# uC-Board.net
KiCad netlist of a schematic drawn in EAGLE
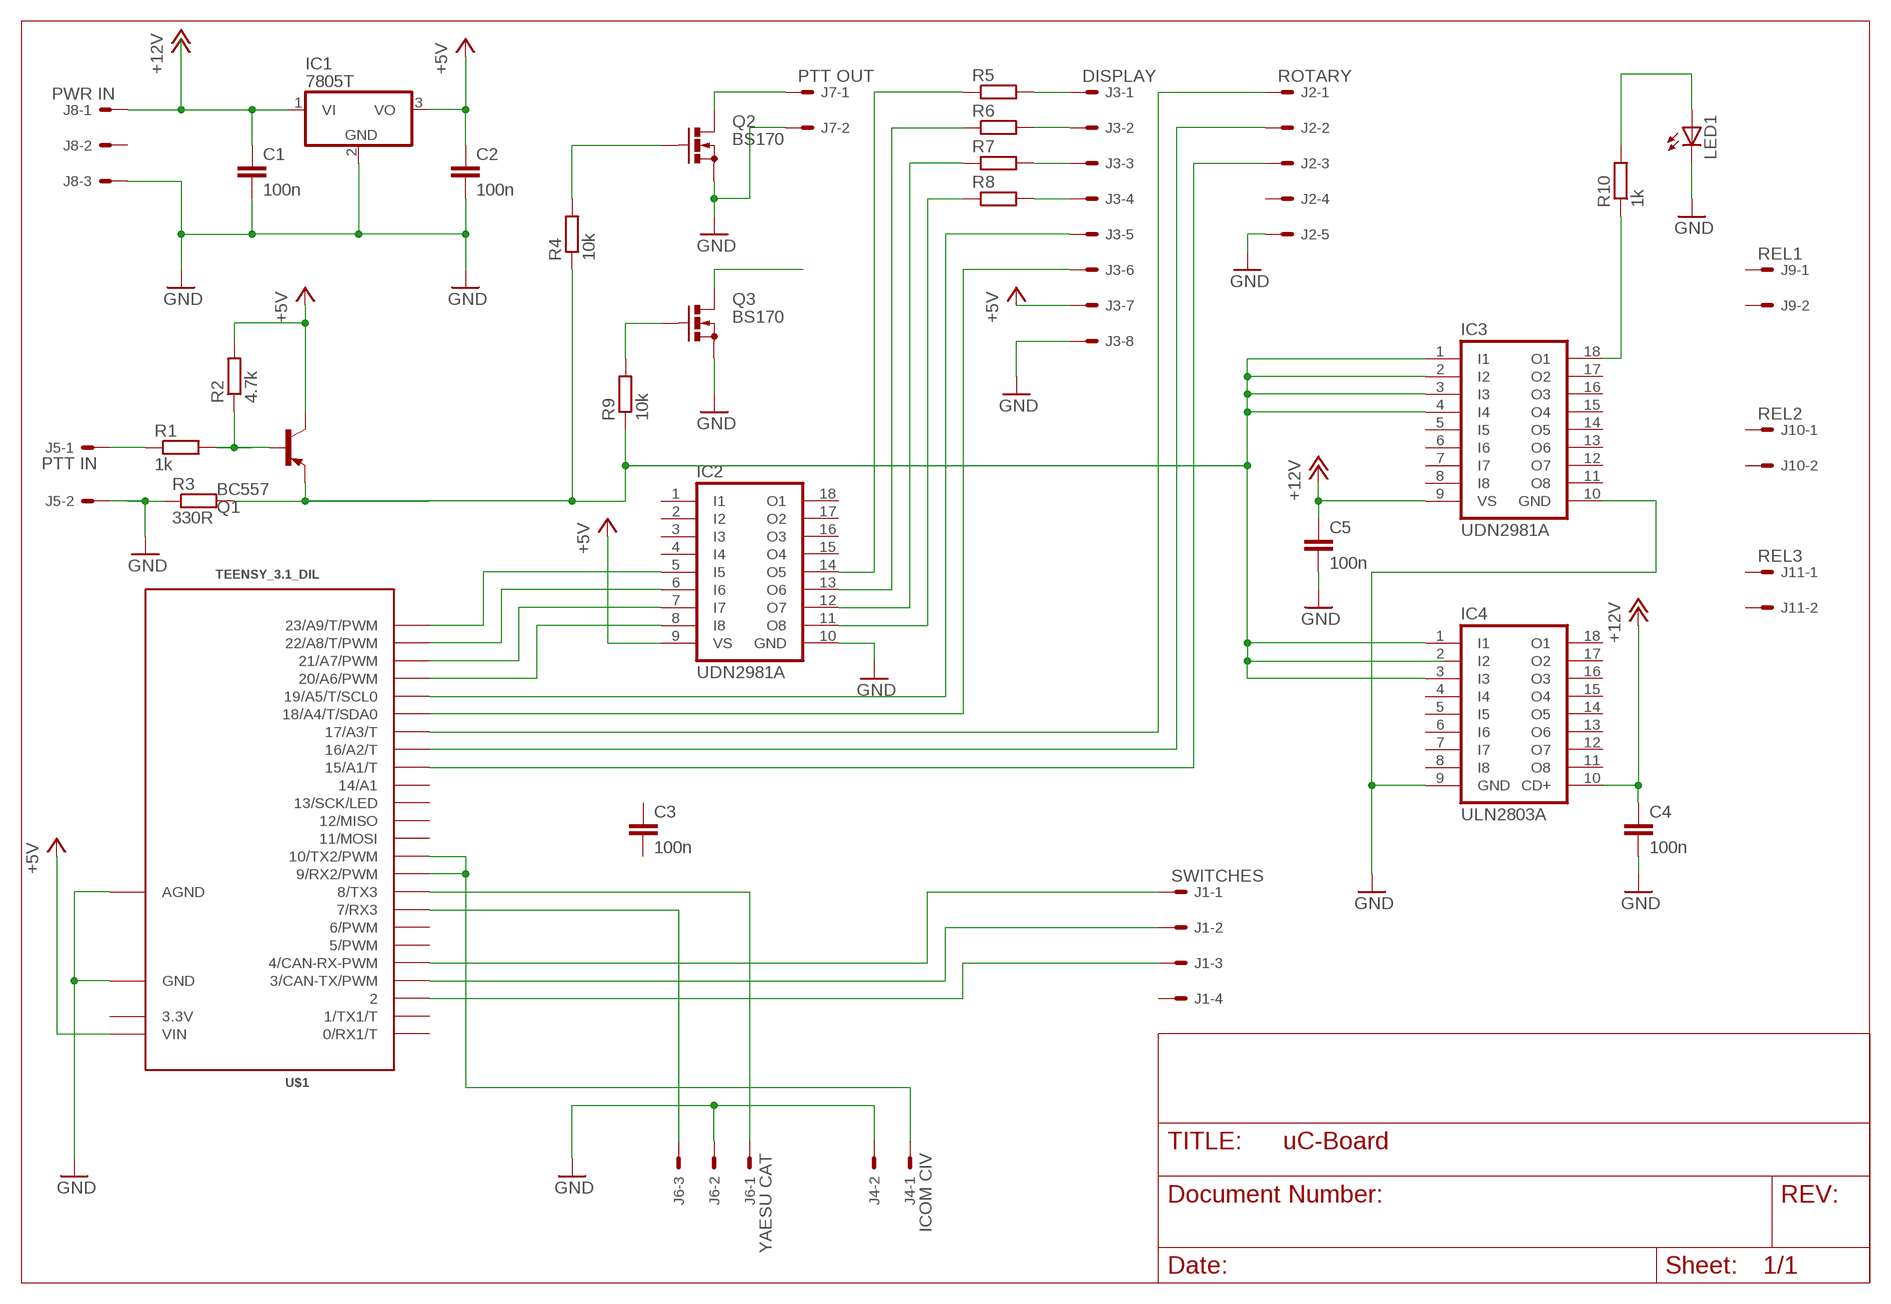
[diagram p0: schematic, sheet 1]

(export (version "E")
  (design (tool "Eeschema 10.0.6"))
  (components
    (comp (ref "C1")
      (value "100n")
      (footprint "eagle-import:C025-025X050")
      (libsource (lib "eagle-import") (part "C-EU025-025X050"))
    )
    (comp (ref "C2")
      (value "100n")
      (footprint "eagle-import:C025-025X050")
      (libsource (lib "eagle-import") (part "C-EU025-025X050"))
    )
    (comp (ref "C3")
      (value "100n")
      (footprint "eagle-import:C025-025X050")
      (libsource (lib "eagle-import") (part "C-EU025-025X050"))
    )
    (comp (ref "C4")
      (value "100n")
      (footprint "eagle-import:C025-025X050")
      (libsource (lib "eagle-import") (part "C-EU025-025X050"))
    )
    (comp (ref "C5")
      (value "100n")
      (footprint "eagle-import:C025-025X050")
      (libsource (lib "eagle-import") (part "C-EU025-025X050"))
    )
    (comp (ref "IC1")
      (value "7805T")
      (footprint "eagle-import:TO220H")
      (libsource (lib "eagle-import") (part "78T05"))
    )
    (comp (ref "IC2")
      (value "UDN2981A")
      (footprint "eagle-import:DIL18")
      (libsource (lib "eagle-import") (part "UDN298A1"))
    )
    (comp (ref "IC3")
      (value "UDN2981A")
      (footprint "eagle-import:DIL18")
      (libsource (lib "eagle-import") (part "UDN298A1"))
    )
    (comp (ref "IC4")
      (value "ULN2803A")
      (footprint "eagle-import:DIL18")
      (libsource (lib "eagle-import") (part "ULN2803A"))
    )
    (comp (ref "J1")
      (value "SWITCHES")
      (footprint "eagle-import:6410-04")
      (libsource (lib "eagle-import") (part "22-?-0427-2041"))
    )
    (comp (ref "J2")
      (value "ROTARY")
      (footprint "eagle-import:6410-05")
      (libsource (lib "eagle-import") (part "22-?-0527-2051"))
    )
    (comp (ref "J3")
      (value "DISPLAY")
      (footprint "eagle-import:6410-08")
      (libsource (lib "eagle-import") (part "22-?-0827-2081"))
    )
    (comp (ref "J4")
      (value "ICOM CIV")
      (footprint "eagle-import:6410-02")
      (libsource (lib "eagle-import") (part "22-?-0227-2021"))
    )
    (comp (ref "J5")
      (value "PTT IN")
      (footprint "eagle-import:6410-02")
      (libsource (lib "eagle-import") (part "22-?-0227-2021"))
    )
    (comp (ref "J6")
      (value "YAESU CAT")
      (footprint "eagle-import:6410-03")
      (libsource (lib "eagle-import") (part "22-?-0327-2031"))
    )
    (comp (ref "J7")
      (value "PTT OUT")
      (footprint "eagle-import:6410-02")
      (libsource (lib "eagle-import") (part "22-?-0227-2021"))
    )
    (comp (ref "J8")
      (value "PWR IN")
      (footprint "eagle-import:22-23-2031")
      (fields (field (name "MF") "MOLEX") (field (name "MPN") "22-23-2031"))
      (libsource (lib "eagle-import") (part "22-23-2031"))
    )
    (comp (ref "J9")
      (value "REL1")
      (footprint "eagle-import:6410-02")
      (libsource (lib "eagle-import") (part "22-?-0227-2021"))
    )
    (comp (ref "J10")
      (value "REL2")
      (footprint "eagle-import:6410-02")
      (libsource (lib "eagle-import") (part "22-?-0227-2021"))
    )
    (comp (ref "J11")
      (value "REL3")
      (footprint "eagle-import:6410-02")
      (libsource (lib "eagle-import") (part "22-?-0227-2021"))
    )
    (comp (ref "LED1")
      (value "LED5MM")
      (footprint "eagle-import:LED5MM")
      (libsource (lib "eagle-import") (part "LED5MM"))
    )
    (comp (ref "Q1")
      (value "BC557")
      (footprint "eagle-import:TO92")
      (libsource (lib "eagle-import") (part "BC557"))
    )
    (comp (ref "Q2")
      (value "BS170")
      (footprint "eagle-import:SOT54E")
      (libsource (lib "eagle-import") (part "BS170"))
    )
    (comp (ref "Q3")
      (value "BS170")
      (footprint "eagle-import:SOT54E")
      (libsource (lib "eagle-import") (part "BS170"))
    )
    (comp (ref "R1")
      (value "1k")
      (footprint "eagle-import:0207_10")
      (libsource (lib "eagle-import") (part "R-EU_0207/10"))
    )
    (comp (ref "R2")
      (value "4.7k")
      (footprint "eagle-import:0207_10")
      (libsource (lib "eagle-import") (part "R-EU_0207/10"))
    )
    (comp (ref "R3")
      (value "330R")
      (footprint "eagle-import:0207_10")
      (libsource (lib "eagle-import") (part "R-EU_0207/10"))
    )
    (comp (ref "R4")
      (value "10k")
      (footprint "eagle-import:0207_10")
      (libsource (lib "eagle-import") (part "R-EU_0207/10"))
    )
    (comp (ref "R5")
      (value "R-EU_0207/10")
      (footprint "eagle-import:0207_10")
      (libsource (lib "eagle-import") (part "R-EU_0207/10"))
    )
    (comp (ref "R6")
      (value "R-EU_0207/10")
      (footprint "eagle-import:0207_10")
      (libsource (lib "eagle-import") (part "R-EU_0207/10"))
    )
    (comp (ref "R7")
      (value "R-EU_0207/10")
      (footprint "eagle-import:0207_10")
      (libsource (lib "eagle-import") (part "R-EU_0207/10"))
    )
    (comp (ref "R8")
      (value "R-EU_0207/10")
      (footprint "eagle-import:0207_10")
      (libsource (lib "eagle-import") (part "R-EU_0207/10"))
    )
    (comp (ref "R9")
      (value "10k")
      (footprint "eagle-import:0207_10")
      (libsource (lib "eagle-import") (part "R-EU_0207/10"))
    )
    (comp (ref "R10")
      (value "1k")
      (footprint "eagle-import:0207_10")
      (libsource (lib "eagle-import") (part "R-EU_0207/10"))
    )
    (comp (ref "U$1")
      (value "TEENSY_3.1_DIL")
      (footprint "eagle-import:TEENSY3-DIL")
      (libsource (lib "eagle-import") (part "TEENSY_3.1_DIL"))
    )
  )
  (nets
    (net (code "1") (name "+5V") (class "Default")
      (node (ref "C2") (pin "1") (pinfunction "1_1") (pintype "passive"))
      (node (ref "IC1") (pin "3") (pinfunction "VO_3") (pintype "passive"))
      (node (ref "IC2") (pin "9") (pinfunction "VS_9") (pintype "passive"))
      (node (ref "J3") (pin "7") (pinfunction "S_7") (pintype "passive"))
      (node (ref "Q1") (pin "3") (pinfunction "C_3") (pintype "passive"))
      (node (ref "R2") (pin "2") (pinfunction "2_2") (pintype "passive"))
      (node (ref "U$1") (pin "VIN") (pinfunction "VIN_VIN") (pintype "power_in"))
    )
    (net (code "2") (name "+12V") (class "Default")
      (node (ref "C1") (pin "1") (pinfunction "1_1") (pintype "passive"))
      (node (ref "C4") (pin "1") (pinfunction "1_1") (pintype "passive"))
      (node (ref "C5") (pin "1") (pinfunction "1_1") (pintype "passive"))
      (node (ref "IC1") (pin "1") (pinfunction "VI_1") (pintype "input"))
      (node (ref "IC3") (pin "9") (pinfunction "VS_9") (pintype "passive"))
      (node (ref "IC4") (pin "10") (pinfunction "CD+_10") (pintype "passive"))
      (node (ref "J8") (pin "1") (pinfunction "S_1") (pintype "passive"))
    )
    (net (code "3") (name "/3.3V") (class "Default")
      (node (ref "U$1") (pin "3.3V") (pinfunction "3.3V_3.3V") (pintype "power_in"))
    )
    (net (code "4") (name "GND") (class "Default")
      (node (ref "C1") (pin "2") (pinfunction "2_2") (pintype "passive"))
      (node (ref "C2") (pin "2") (pinfunction "2_2") (pintype "passive"))
      (node (ref "C4") (pin "2") (pinfunction "2_2") (pintype "passive"))
      (node (ref "C5") (pin "2") (pinfunction "2_2") (pintype "passive"))
      (node (ref "IC1") (pin "2") (pinfunction "GND_2") (pintype "passive"))
      (node (ref "IC2") (pin "10") (pinfunction "GND_10") (pintype "power_in"))
      (node (ref "IC3") (pin "10") (pinfunction "GND_10") (pintype "power_in"))
      (node (ref "IC4") (pin "9") (pinfunction "GND_9") (pintype "power_in"))
      (node (ref "J2") (pin "5") (pinfunction "S_5") (pintype "passive"))
      (node (ref "J3") (pin "8") (pinfunction "S_8") (pintype "passive"))
      (node (ref "J4") (pin "2") (pinfunction "S_2") (pintype "passive"))
      (node (ref "J5") (pin "2") (pinfunction "S_2") (pintype "passive"))
      (node (ref "J6") (pin "2") (pinfunction "S_2") (pintype "passive"))
      (node (ref "J7") (pin "2") (pinfunction "S_2") (pintype "passive"))
      (node (ref "J8") (pin "3") (pinfunction "S_3") (pintype "passive"))
      (node (ref "LED1") (pin "K") (pinfunction "C_K") (pintype "passive"))
      (node (ref "Q2") (pin "S") (pinfunction "S_S") (pintype "passive"))
      (node (ref "Q3") (pin "S") (pinfunction "S_S") (pintype "passive"))
      (node (ref "R3") (pin "1") (pinfunction "1_1") (pintype "passive"))
      (node (ref "U$1") (pin "AGND") (pinfunction "AGND_AGND") (pintype "power_in"))
      (node (ref "U$1") (pin "GND") (pinfunction "GND_GND") (pintype "power_in"))
    )
    (net (code "5") (name "Net-(IC2-I5)") (class "Default")
      (node (ref "IC2") (pin "5") (pinfunction "I5_5") (pintype "input"))
      (node (ref "U$1") (pin "23/A9") (pinfunction "23/A9/T/PWM_23/A9") (pintype "bidirectional"))
    )
    (net (code "6") (name "Net-(IC2-I6)") (class "Default")
      (node (ref "IC2") (pin "6") (pinfunction "I6_6") (pintype "input"))
      (node (ref "U$1") (pin "22/A8") (pinfunction "22/A8/T/PWM_22/A8") (pintype "bidirectional"))
    )
    (net (code "7") (name "Net-(IC2-I7)") (class "Default")
      (node (ref "IC2") (pin "7") (pinfunction "I7_7") (pintype "input"))
      (node (ref "U$1") (pin "21/A7") (pinfunction "21/A7/PWM_21/A7") (pintype "bidirectional"))
    )
    (net (code "8") (name "Net-(IC2-I8)") (class "Default")
      (node (ref "IC2") (pin "8") (pinfunction "I8_8") (pintype "input"))
      (node (ref "U$1") (pin "20/A6") (pinfunction "20/A6/PWM_20/A6") (pintype "bidirectional"))
    )
    (net (code "9") (name "Net-(IC2-O5)") (class "Default")
      (node (ref "IC2") (pin "14") (pinfunction "O5_14") (pintype "open_collector"))
      (node (ref "R5") (pin "1") (pinfunction "1_1") (pintype "passive"))
    )
    (net (code "10") (name "Net-(IC2-O6)") (class "Default")
      (node (ref "IC2") (pin "13") (pinfunction "O6_13") (pintype "open_collector"))
      (node (ref "R6") (pin "1") (pinfunction "1_1") (pintype "passive"))
    )
    (net (code "11") (name "Net-(IC2-O7)") (class "Default")
      (node (ref "IC2") (pin "12") (pinfunction "O7_12") (pintype "open_collector"))
      (node (ref "R7") (pin "1") (pinfunction "1_1") (pintype "passive"))
    )
    (net (code "12") (name "Net-(IC2-O8)") (class "Default")
      (node (ref "IC2") (pin "11") (pinfunction "O8_11") (pintype "open_collector"))
      (node (ref "R8") (pin "1") (pinfunction "1_1") (pintype "passive"))
    )
    (net (code "13") (name "Net-(IC3-I1)") (class "Default")
      (node (ref "IC3") (pin "1") (pinfunction "I1_1") (pintype "input"))
      (node (ref "IC3") (pin "2") (pinfunction "I2_2") (pintype "input"))
      (node (ref "IC3") (pin "3") (pinfunction "I3_3") (pintype "input"))
      (node (ref "IC3") (pin "4") (pinfunction "I4_4") (pintype "input"))
      (node (ref "IC4") (pin "1") (pinfunction "I1_1") (pintype "input"))
      (node (ref "IC4") (pin "3") (pinfunction "I3_3") (pintype "input"))
      (node (ref "Q1") (pin "1") (pinfunction "E_1") (pintype "passive"))
      (node (ref "R3") (pin "2") (pinfunction "2_2") (pintype "passive"))
      (node (ref "R4") (pin "1") (pinfunction "1_1") (pintype "passive"))
      (node (ref "R9") (pin "1") (pinfunction "1_1") (pintype "passive"))
    )
    (net (code "14") (name "Net-(IC3-O1)") (class "Default")
      (node (ref "IC3") (pin "18") (pinfunction "O1_18") (pintype "open_collector"))
      (node (ref "R10") (pin "1") (pinfunction "1_1") (pintype "passive"))
    )
    (net (code "15") (name "Net-(J1A-S)") (class "Default")
      (node (ref "J1") (pin "1") (pinfunction "S_1") (pintype "passive"))
      (node (ref "U$1") (pin "4") (pinfunction "4/CAN-RX-PWM_4") (pintype "bidirectional"))
    )
    (net (code "16") (name "Net-(J1B-S)") (class "Default")
      (node (ref "J1") (pin "2") (pinfunction "S_2") (pintype "passive"))
      (node (ref "U$1") (pin "3") (pinfunction "3/CAN-TX/PWM_3") (pintype "bidirectional"))
    )
    (net (code "17") (name "Net-(J1C-S)") (class "Default")
      (node (ref "J1") (pin "3") (pinfunction "S_3") (pintype "passive"))
      (node (ref "U$1") (pin "2") (pinfunction "2_2") (pintype "bidirectional"))
    )
    (net (code "18") (name "Net-(J2A-S)") (class "Default")
      (node (ref "J2") (pin "1") (pinfunction "S_1") (pintype "passive"))
      (node (ref "U$1") (pin "17/A3") (pinfunction "17/A3/T_17/A3") (pintype "bidirectional"))
    )
    (net (code "19") (name "Net-(J2B-S)") (class "Default")
      (node (ref "J2") (pin "2") (pinfunction "S_2") (pintype "passive"))
      (node (ref "U$1") (pin "16/A2") (pinfunction "16/A2/T_16/A2") (pintype "bidirectional"))
    )
    (net (code "20") (name "Net-(J2C-S)") (class "Default")
      (node (ref "J2") (pin "3") (pinfunction "S_3") (pintype "passive"))
      (node (ref "U$1") (pin "15/A1") (pinfunction "15/A1/T_15/A1") (pintype "bidirectional"))
    )
    (net (code "21") (name "Net-(J3A-S)") (class "Default")
      (node (ref "J3") (pin "1") (pinfunction "S_1") (pintype "passive"))
      (node (ref "R5") (pin "2") (pinfunction "2_2") (pintype "passive"))
    )
    (net (code "22") (name "Net-(J3B-S)") (class "Default")
      (node (ref "J3") (pin "2") (pinfunction "S_2") (pintype "passive"))
      (node (ref "R6") (pin "2") (pinfunction "2_2") (pintype "passive"))
    )
    (net (code "23") (name "Net-(J3C-S)") (class "Default")
      (node (ref "J3") (pin "3") (pinfunction "S_3") (pintype "passive"))
      (node (ref "R7") (pin "2") (pinfunction "2_2") (pintype "passive"))
    )
    (net (code "24") (name "Net-(J3D-S)") (class "Default")
      (node (ref "J3") (pin "4") (pinfunction "S_4") (pintype "passive"))
      (node (ref "R8") (pin "2") (pinfunction "2_2") (pintype "passive"))
    )
    (net (code "25") (name "Net-(J3E-S)") (class "Default")
      (node (ref "J3") (pin "5") (pinfunction "S_5") (pintype "passive"))
      (node (ref "U$1") (pin "19/A5") (pinfunction "19/A5/T/SCL0_19/A5") (pintype "bidirectional"))
    )
    (net (code "26") (name "Net-(J3F-S)") (class "Default")
      (node (ref "J3") (pin "6") (pinfunction "S_6") (pintype "passive"))
      (node (ref "U$1") (pin "18/A4") (pinfunction "18/A4/T/SDA0_18/A4") (pintype "bidirectional"))
    )
    (net (code "27") (name "Net-(J4A-S)") (class "Default")
      (node (ref "J4") (pin "1") (pinfunction "S_1") (pintype "passive"))
      (node (ref "U$1") (pin "10") (pinfunction "10/TX2/PWM_10") (pintype "bidirectional"))
      (node (ref "U$1") (pin "9") (pinfunction "9/RX2/PWM_9") (pintype "bidirectional"))
    )
    (net (code "28") (name "Net-(J5A-S)") (class "Default")
      (node (ref "J5") (pin "1") (pinfunction "S_1") (pintype "passive"))
      (node (ref "R1") (pin "1") (pinfunction "1_1") (pintype "passive"))
    )
    (net (code "29") (name "Net-(J6A-S)") (class "Default")
      (node (ref "J6") (pin "1") (pinfunction "S_1") (pintype "passive"))
      (node (ref "U$1") (pin "8") (pinfunction "8/TX3_8") (pintype "bidirectional"))
    )
    (net (code "30") (name "Net-(J6C-S)") (class "Default")
      (node (ref "J6") (pin "3") (pinfunction "S_3") (pintype "passive"))
      (node (ref "U$1") (pin "7") (pinfunction "7/RX3_7") (pintype "bidirectional"))
    )
    (net (code "31") (name "Net-(J7A-S)") (class "Default")
      (node (ref "J7") (pin "1") (pinfunction "S_1") (pintype "passive"))
      (node (ref "Q2") (pin "D") (pinfunction "D_D") (pintype "passive"))
    )
    (net (code "32") (name "Net-(LED1-PadA)") (class "Default")
      (node (ref "LED1") (pin "A") (pinfunction "A_A") (pintype "passive"))
      (node (ref "R10") (pin "2") (pinfunction "2_2") (pintype "passive"))
    )
    (net (code "33") (name "Net-(Q1-B)") (class "Default")
      (node (ref "Q1") (pin "2") (pinfunction "B_2") (pintype "passive"))
      (node (ref "R1") (pin "2") (pinfunction "2_2") (pintype "passive"))
      (node (ref "R2") (pin "1") (pinfunction "1_1") (pintype "passive"))
    )
    (net (code "34") (name "Net-(Q2-PadG)") (class "Default")
      (node (ref "Q2") (pin "G") (pinfunction "G_G") (pintype "passive"))
      (node (ref "R4") (pin "2") (pinfunction "2_2") (pintype "passive"))
    )
    (net (code "35") (name "Net-(Q3-PadG)") (class "Default")
      (node (ref "Q3") (pin "G") (pinfunction "G_G") (pintype "passive"))
      (node (ref "R9") (pin "2") (pinfunction "2_2") (pintype "passive"))
    )
    (net (code "36") (name "unconnected-(C3-Pad1)") (class "Default")
      (node (ref "C3") (pin "1") (pinfunction "1_1") (pintype "passive"))
    )
    (net (code "37") (name "unconnected-(C3-Pad2)") (class "Default")
      (node (ref "C3") (pin "2") (pinfunction "2_2") (pintype "passive"))
    )
    (net (code "38") (name "unconnected-(IC2-I1-Pad1)") (class "Default")
      (node (ref "IC2") (pin "1") (pinfunction "I1_1") (pintype "input"))
    )
    (net (code "39") (name "unconnected-(IC2-I2-Pad2)") (class "Default")
      (node (ref "IC2") (pin "2") (pinfunction "I2_2") (pintype "input"))
    )
    (net (code "40") (name "unconnected-(IC2-I3-Pad3)") (class "Default")
      (node (ref "IC2") (pin "3") (pinfunction "I3_3") (pintype "input"))
    )
    (net (code "41") (name "unconnected-(IC2-I4-Pad4)") (class "Default")
      (node (ref "IC2") (pin "4") (pinfunction "I4_4") (pintype "input"))
    )
    (net (code "42") (name "unconnected-(IC2-O1-Pad18)") (class "Default")
      (node (ref "IC2") (pin "18") (pinfunction "O1_18") (pintype "open_collector"))
    )
    (net (code "43") (name "unconnected-(IC2-O2-Pad17)") (class "Default")
      (node (ref "IC2") (pin "17") (pinfunction "O2_17") (pintype "open_collector"))
    )
    (net (code "44") (name "unconnected-(IC2-O3-Pad16)") (class "Default")
      (node (ref "IC2") (pin "16") (pinfunction "O3_16") (pintype "open_collector"))
    )
    (net (code "45") (name "unconnected-(IC2-O4-Pad15)") (class "Default")
      (node (ref "IC2") (pin "15") (pinfunction "O4_15") (pintype "open_collector"))
    )
    (net (code "46") (name "unconnected-(IC3-I5-Pad5)") (class "Default")
      (node (ref "IC3") (pin "5") (pinfunction "I5_5") (pintype "input"))
    )
    (net (code "47") (name "unconnected-(IC3-I6-Pad6)") (class "Default")
      (node (ref "IC3") (pin "6") (pinfunction "I6_6") (pintype "input"))
    )
    (net (code "48") (name "unconnected-(IC3-I7-Pad7)") (class "Default")
      (node (ref "IC3") (pin "7") (pinfunction "I7_7") (pintype "input"))
    )
    (net (code "49") (name "unconnected-(IC3-I8-Pad8)") (class "Default")
      (node (ref "IC3") (pin "8") (pinfunction "I8_8") (pintype "input"))
    )
    (net (code "50") (name "unconnected-(IC3-O2-Pad17)") (class "Default")
      (node (ref "IC3") (pin "17") (pinfunction "O2_17") (pintype "open_collector"))
    )
    (net (code "51") (name "unconnected-(IC3-O3-Pad16)") (class "Default")
      (node (ref "IC3") (pin "16") (pinfunction "O3_16") (pintype "open_collector"))
    )
    (net (code "52") (name "unconnected-(IC3-O4-Pad15)") (class "Default")
      (node (ref "IC3") (pin "15") (pinfunction "O4_15") (pintype "open_collector"))
    )
    (net (code "53") (name "unconnected-(IC3-O5-Pad14)") (class "Default")
      (node (ref "IC3") (pin "14") (pinfunction "O5_14") (pintype "open_collector"))
    )
    (net (code "54") (name "unconnected-(IC3-O6-Pad13)") (class "Default")
      (node (ref "IC3") (pin "13") (pinfunction "O6_13") (pintype "open_collector"))
    )
    (net (code "55") (name "unconnected-(IC3-O7-Pad12)") (class "Default")
      (node (ref "IC3") (pin "12") (pinfunction "O7_12") (pintype "open_collector"))
    )
    (net (code "56") (name "unconnected-(IC3-O8-Pad11)") (class "Default")
      (node (ref "IC3") (pin "11") (pinfunction "O8_11") (pintype "open_collector"))
    )
    (net (code "57") (name "unconnected-(IC4-I2-Pad2)") (class "Default")
      (node (ref "IC4") (pin "2") (pinfunction "I2_2") (pintype "input"))
    )
    (net (code "58") (name "unconnected-(IC4-I4-Pad4)") (class "Default")
      (node (ref "IC4") (pin "4") (pinfunction "I4_4") (pintype "input"))
    )
    (net (code "59") (name "unconnected-(IC4-I5-Pad5)") (class "Default")
      (node (ref "IC4") (pin "5") (pinfunction "I5_5") (pintype "input"))
    )
    (net (code "60") (name "unconnected-(IC4-I6-Pad6)") (class "Default")
      (node (ref "IC4") (pin "6") (pinfunction "I6_6") (pintype "input"))
    )
    (net (code "61") (name "unconnected-(IC4-I7-Pad7)") (class "Default")
      (node (ref "IC4") (pin "7") (pinfunction "I7_7") (pintype "input"))
    )
    (net (code "62") (name "unconnected-(IC4-I8-Pad8)") (class "Default")
      (node (ref "IC4") (pin "8") (pinfunction "I8_8") (pintype "input"))
    )
    (net (code "63") (name "unconnected-(IC4-O1-Pad18)") (class "Default")
      (node (ref "IC4") (pin "18") (pinfunction "O1_18") (pintype "open_collector"))
    )
    (net (code "64") (name "unconnected-(IC4-O2-Pad17)") (class "Default")
      (node (ref "IC4") (pin "17") (pinfunction "O2_17") (pintype "open_collector"))
    )
    (net (code "65") (name "unconnected-(IC4-O3-Pad16)") (class "Default")
      (node (ref "IC4") (pin "16") (pinfunction "O3_16") (pintype "open_collector"))
    )
    (net (code "66") (name "unconnected-(IC4-O4-Pad15)") (class "Default")
      (node (ref "IC4") (pin "15") (pinfunction "O4_15") (pintype "open_collector"))
    )
    (net (code "67") (name "unconnected-(IC4-O5-Pad14)") (class "Default")
      (node (ref "IC4") (pin "14") (pinfunction "O5_14") (pintype "open_collector"))
    )
    (net (code "68") (name "unconnected-(IC4-O6-Pad13)") (class "Default")
      (node (ref "IC4") (pin "13") (pinfunction "O6_13") (pintype "open_collector"))
    )
    (net (code "69") (name "unconnected-(IC4-O7-Pad12)") (class "Default")
      (node (ref "IC4") (pin "12") (pinfunction "O7_12") (pintype "open_collector"))
    )
    (net (code "70") (name "unconnected-(IC4-O8-Pad11)") (class "Default")
      (node (ref "IC4") (pin "11") (pinfunction "O8_11") (pintype "open_collector"))
    )
    (net (code "71") (name "unconnected-(J1D-S-Pad4)") (class "Default")
      (node (ref "J1") (pin "4") (pinfunction "S_4") (pintype "passive"))
    )
    (net (code "72") (name "unconnected-(J2D-S-Pad4)") (class "Default")
      (node (ref "J2") (pin "4") (pinfunction "S_4") (pintype "passive"))
    )
    (net (code "73") (name "unconnected-(J8B-S-Pad2)") (class "Default")
      (node (ref "J8") (pin "2") (pinfunction "S_2") (pintype "passive"))
    )
    (net (code "74") (name "unconnected-(J9A-S-Pad1)") (class "Default")
      (node (ref "J9") (pin "1") (pinfunction "S_1") (pintype "passive"))
    )
    (net (code "75") (name "unconnected-(J9B-S-Pad2)") (class "Default")
      (node (ref "J9") (pin "2") (pinfunction "S_2") (pintype "passive"))
    )
    (net (code "76") (name "unconnected-(J10A-S-Pad1)") (class "Default")
      (node (ref "J10") (pin "1") (pinfunction "S_1") (pintype "passive"))
    )
    (net (code "77") (name "unconnected-(J10B-S-Pad2)") (class "Default")
      (node (ref "J10") (pin "2") (pinfunction "S_2") (pintype "passive"))
    )
    (net (code "78") (name "unconnected-(J11A-S-Pad1)") (class "Default")
      (node (ref "J11") (pin "1") (pinfunction "S_1") (pintype "passive"))
    )
    (net (code "79") (name "unconnected-(J11B-S-Pad2)") (class "Default")
      (node (ref "J11") (pin "2") (pinfunction "S_2") (pintype "passive"))
    )
    (net (code "80") (name "unconnected-(Q3-PadD)") (class "Default")
      (node (ref "Q3") (pin "D") (pinfunction "D_D") (pintype "passive"))
    )
    (net (code "81") (name "unconnected-(U$1-0{slash}RX1{slash}T-Pad0)") (class "Default")
      (node (ref "U$1") (pin "0") (pinfunction "0/RX1/T_0") (pintype "bidirectional"))
    )
    (net (code "82") (name "unconnected-(U$1-1{slash}TX1{slash}T-Pad1)") (class "Default")
      (node (ref "U$1") (pin "1") (pinfunction "1/TX1/T_1") (pintype "bidirectional"))
    )
    (net (code "83") (name "unconnected-(U$1-5{slash}PWM-Pad5)") (class "Default")
      (node (ref "U$1") (pin "5") (pinfunction "5/PWM_5") (pintype "bidirectional"))
    )
    (net (code "84") (name "unconnected-(U$1-6{slash}PWM-Pad6)") (class "Default")
      (node (ref "U$1") (pin "6") (pinfunction "6/PWM_6") (pintype "bidirectional"))
    )
    (net (code "85") (name "unconnected-(U$1-11{slash}MOSI-Pad11)") (class "Default")
      (node (ref "U$1") (pin "11") (pinfunction "11/MOSI_11") (pintype "bidirectional"))
    )
    (net (code "86") (name "unconnected-(U$1-12{slash}MISO-Pad12)") (class "Default")
      (node (ref "U$1") (pin "12") (pinfunction "12/MISO_12") (pintype "bidirectional"))
    )
    (net (code "87") (name "unconnected-(U$1-13{slash}SCK{slash}LED-Pad13)") (class "Default")
      (node (ref "U$1") (pin "13") (pinfunction "13/SCK/LED_13") (pintype "bidirectional"))
    )
    (net (code "88") (name "unconnected-(U$1-14{slash}A1-Pad14{slash}A0)") (class "Default")
      (node (ref "U$1") (pin "14/A0") (pinfunction "14/A1_14/A0") (pintype "bidirectional"))
    )
  )
)
